# DenkyD4.net
KiCad netlist of a schematic drawn in EAGLE
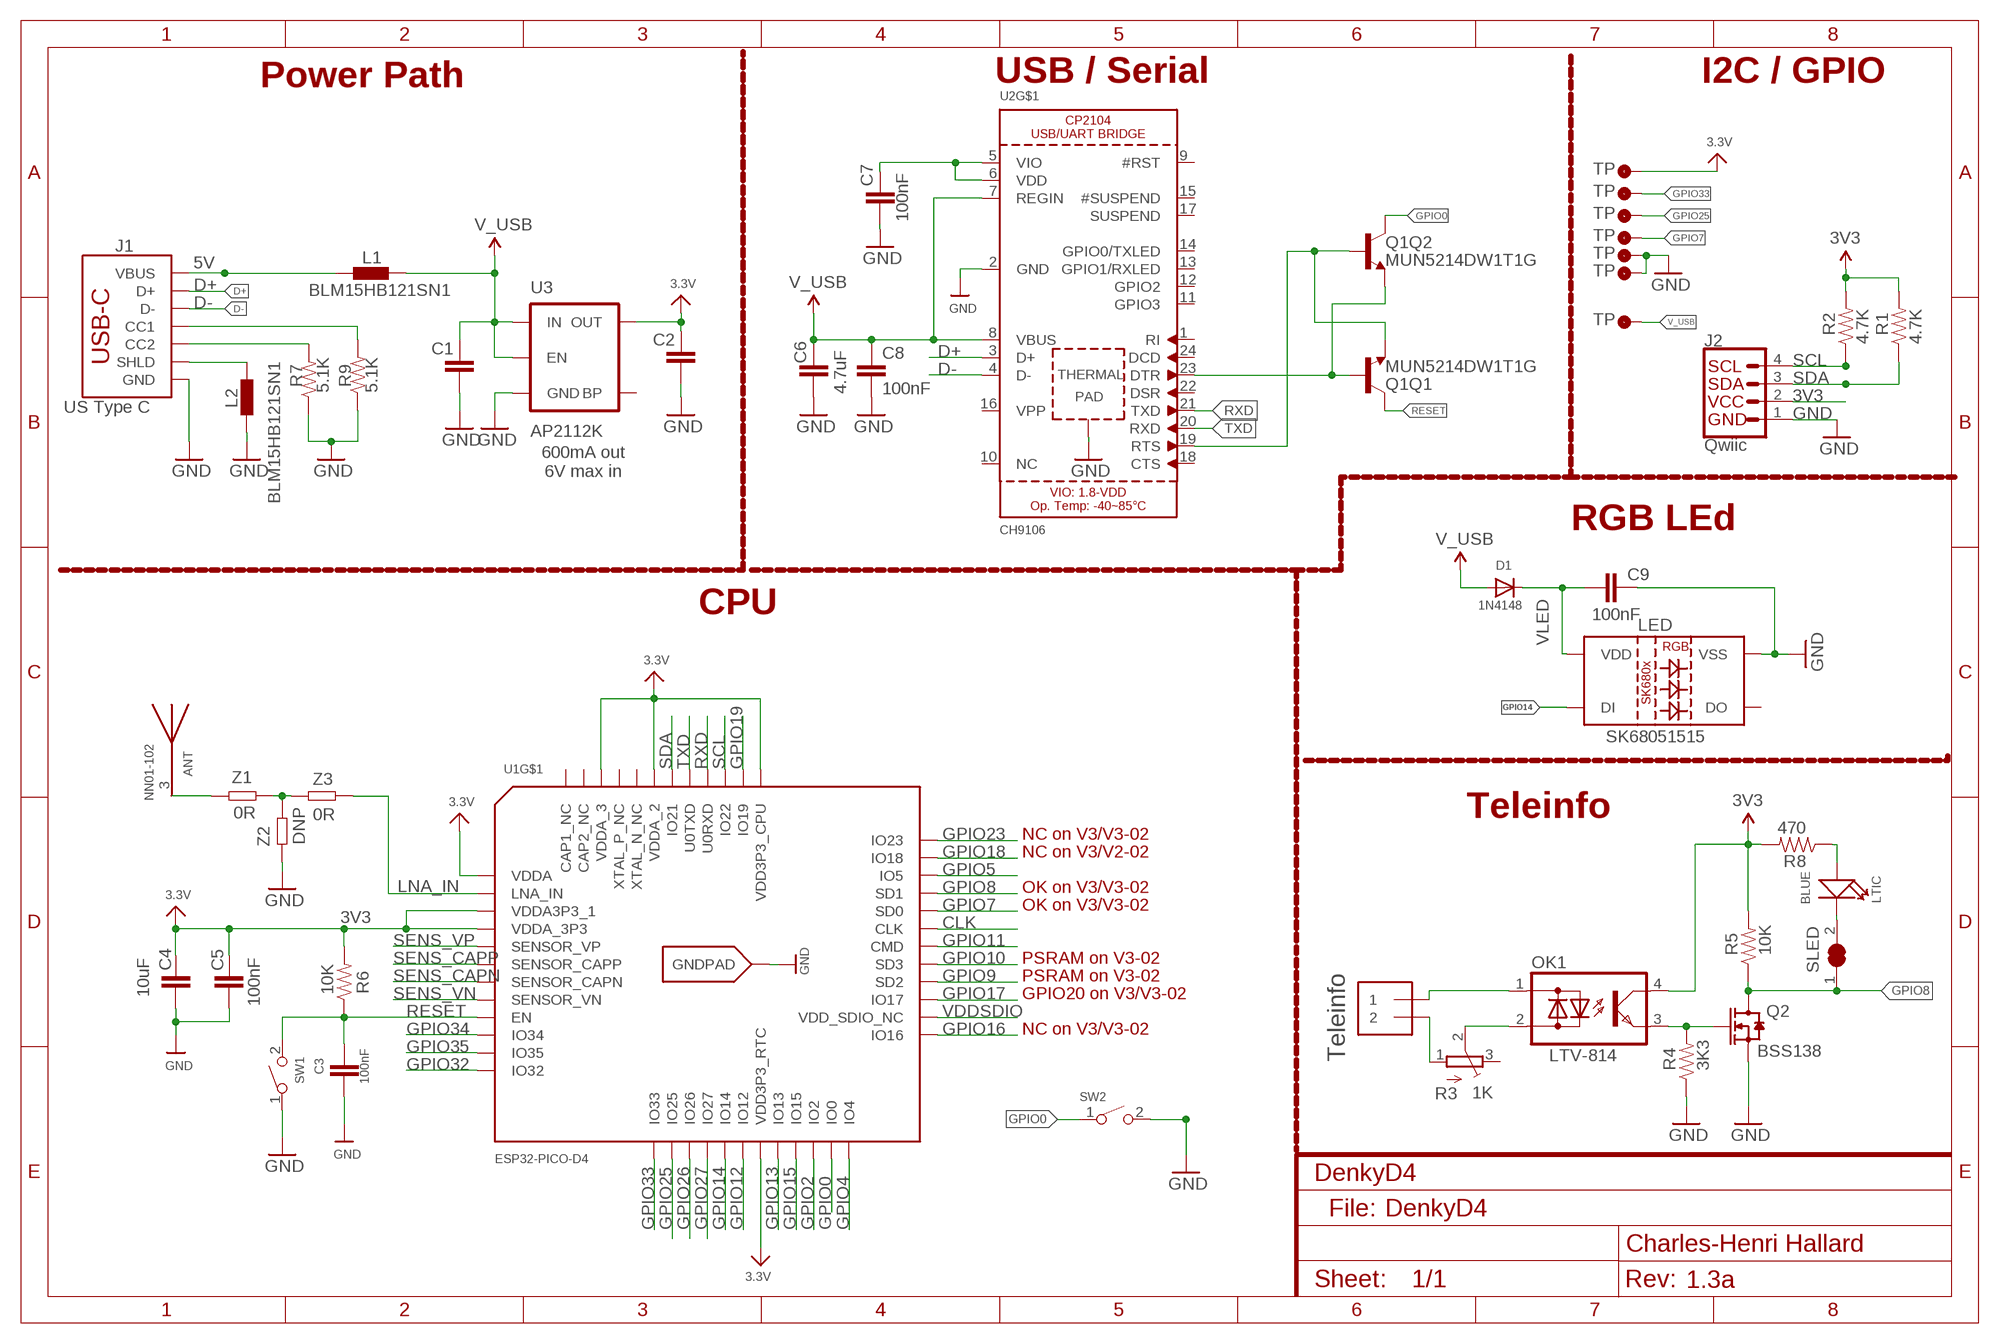
[diagram p0: schematic, sheet 1]

(export (version "E")
  (design (tool "Eeschema 10.0.6"))
  (components
    (comp (ref "ANT")
      (value "NN01-102")
      (footprint "eagle-import:XCVR_NN03-320")
      (libsource (lib "eagle-import") (part "NN01-102320"))
    )
    (comp (ref "C1")
      (value "1.0uF")
      (footprint "eagle-import:0402-CAP-OK")
      (libsource (lib "eagle-import") (part "CAP0402-CAP-OK"))
    )
    (comp (ref "C2")
      (value "1.0uF")
      (footprint "eagle-import:0402-CAP-OK")
      (libsource (lib "eagle-import") (part "CAP0402-CAP-OK"))
    )
    (comp (ref "C3")
      (value "100nF")
      (footprint "eagle-import:0402-CAP-OK")
      (libsource (lib "eagle-import") (part "CAP0402-CAP-OK"))
    )
    (comp (ref "C4")
      (value "10uF")
      (footprint "eagle-import:0402-CAP-OK")
      (libsource (lib "eagle-import") (part "CAP0402-CAP-OK"))
    )
    (comp (ref "C5")
      (value "100nF")
      (footprint "eagle-import:0402-CAP-OK")
      (libsource (lib "eagle-import") (part "CAP0402-CAP-OK"))
    )
    (comp (ref "C6")
      (value "4.7uF")
      (footprint "eagle-import:0402-CAP-OK")
      (libsource (lib "eagle-import") (part "CAP0402-CAP-OK"))
    )
    (comp (ref "C7")
      (value "100nF")
      (footprint "eagle-import:0402-CAP-OK")
      (libsource (lib "eagle-import") (part "CAP0402-CAP-OK"))
    )
    (comp (ref "C8")
      (value "100nF")
      (footprint "eagle-import:0402-CAP-OK")
      (libsource (lib "eagle-import") (part "CAP0402-CAP-OK"))
    )
    (comp (ref "C9")
      (value "100nF")
      (footprint "eagle-import:0402-CAP-OK")
      (libsource (lib "eagle-import") (part "CAP0402-CAP-OK"))
    )
    (comp (ref "D1")
      (value "1N4148")
      (footprint "eagle-import:SOD-523")
      (libsource (lib "eagle-import") (part "DIODESOD-523"))
    )
    (comp (ref "J1")
      (value "US Type C")
      (footprint "eagle-import:USB-C-16P-4LAYER-ISOLATED")
      (libsource (lib "eagle-import") (part "USB_C_4-LAYER-ISOLATED"))
    )
    (comp (ref "J2")
      (value "Qwiic")
      (footprint "eagle-import:JST04_1MM_VERT")
      (libsource (lib "eagle-import") (part "QWIIC_CONNECTOR"))
    )
    (comp (ref "J3")
      (value "KF2EDGR-3.81-2P")
      (footprint "eagle-import:1X2-3.5MM")
      (libsource (lib "eagle-import") (part "1X2-3.5MM-3.5MM"))
    )
    (comp (ref "L1")
      (value "BLM15HB121SN1")
      (footprint "eagle-import:0402")
      (libsource (lib "eagle-import") (part "BLM15HB121SN1"))
    )
    (comp (ref "L2")
      (value "BLM15HB121SN1")
      (footprint "eagle-import:0402")
      (libsource (lib "eagle-import") (part "BLM15HB121SN1"))
    )
    (comp (ref "LED")
      (value "SK68051515")
      (footprint "eagle-import:SK6805-1515")
      (libsource (lib "eagle-import") (part "SK68051515"))
    )
    (comp (ref "LTIC")
      (value "BLUE")
      (footprint "eagle-import:LED-0402")
      (fields (field (name "MPN") "BL-HB337A-AV-TRB"))
      (libsource (lib "eagle-import") (part "SMD-LED-CLEAR-BLUE(0402)"))
    )
    (comp (ref "OK1")
      (value "LTV-814")
      (footprint "eagle-import:DIL4-SMD")
      (fields (field (name "MF") "VISHAY/TELEFUNKEN") (field (name "MPN") "SFH6206-3"))
      (libsource (lib "eagle-import") (part "SFH6206"))
    )
    (comp (ref "Q1")
      (value "MUN5214DW1T1G")
      (footprint "eagle-import:DUAL_NPN_SC70-6")
      (libsource (lib "eagle-import") (part "MBT3904DW1T1"))
    )
    (comp (ref "Q2")
      (value "BSS138")
      (footprint "eagle-import:SOT-323-3")
      (libsource (lib "eagle-import") (part "SMD-MOSFET-N-CH-20V-2.1A-CJ2302(SOT-23)"))
    )
    (comp (ref "R1")
      (value "4.7K")
      (footprint "eagle-import:0402-RES")
      (libsource (lib "eagle-import") (part "_c2h_RESISTOR0402-RES"))
    )
    (comp (ref "R2")
      (value "4.7K")
      (footprint "eagle-import:0402-RES")
      (libsource (lib "eagle-import") (part "_c2h_RESISTOR0402-RES"))
    )
    (comp (ref "R3")
      (value "1K")
      (footprint "eagle-import:TC33X")
      (libsource (lib "eagle-import") (part "TRIMPOTTC33X"))
    )
    (comp (ref "R4")
      (value "3K3")
      (footprint "eagle-import:0402-RES")
      (libsource (lib "eagle-import") (part "_c2h_RESISTOR0402-RES"))
    )
    (comp (ref "R5")
      (value "10K")
      (footprint "eagle-import:0402-RES")
      (libsource (lib "eagle-import") (part "_c2h_RESISTOR0402-RES"))
    )
    (comp (ref "R6")
      (value "10K")
      (footprint "eagle-import:0402-RES")
      (libsource (lib "eagle-import") (part "_c2h_RESISTOR0402-RES"))
    )
    (comp (ref "R7")
      (value "5.1K")
      (footprint "eagle-import:0402-RES")
      (libsource (lib "eagle-import") (part "_c2h_RESISTOR0402-RES"))
    )
    (comp (ref "R8")
      (value "470")
      (footprint "eagle-import:0402-RES")
      (libsource (lib "eagle-import") (part "RESISTOR0402-RES"))
    )
    (comp (ref "R9")
      (value "5.1K")
      (footprint "eagle-import:0402-RES")
      (libsource (lib "eagle-import") (part "_c2h_RESISTOR0402-RES"))
    )
    (comp (ref "SLED")
      (value "SOLDERJUMPER_CLOSED")
      (footprint "eagle-import:SOLDERJUMPER_CLOSEDWIRE")
      (libsource (lib "eagle-import") (part "SOLDERJUMPER_CLOSED"))
    )
    (comp (ref "SW1")
      (value "RESET")
      (footprint "eagle-import:C498294")
      (libsource (lib "eagle-import") (part "SMD-BUTTON(2P-3.0X2.5X1.2+0.4MM)"))
    )
    (comp (ref "SW2")
      (value "SMD-BUTTON(2P-3.0X2.5X1.2+0.4MM)")
      (footprint "eagle-import:C498294")
      (libsource (lib "eagle-import") (part "SMD-BUTTON(2P-3.0X2.5X1.2+0.4MM)"))
    )
    (comp (ref "TGG")
      (value "TP3")
      (footprint "eagle-import:TP60_BOT")
      (libsource (lib "eagle-import") (part "TP3"))
    )
    (comp (ref "TGG1")
      (value "TP3")
      (footprint "eagle-import:TP60_BOT")
      (libsource (lib "eagle-import") (part "TP3"))
    )
    (comp (ref "TGG2")
      (value "TP3")
      (footprint "eagle-import:TP60_BOT")
      (libsource (lib "eagle-import") (part "TP3"))
    )
    (comp (ref "TP3")
      (value "TP3")
      (footprint "eagle-import:TP60_BOT")
      (libsource (lib "eagle-import") (part "TP3"))
    )
    (comp (ref "U$3")
      (value "TP3")
      (footprint "eagle-import:TP60_BOT")
      (libsource (lib "eagle-import") (part "TP3"))
    )
    (comp (ref "U$6")
      (value "TP3")
      (footprint "eagle-import:TP60_BOT")
      (libsource (lib "eagle-import") (part "TP3"))
    )
    (comp (ref "U$11")
      (value "TP3")
      (footprint "eagle-import:TP60_BOT")
      (libsource (lib "eagle-import") (part "TP3"))
    )
    (comp (ref "U1")
      (value "ESP32-PICO-D4")
      (footprint "eagle-import:PICO-D4-QFN48")
      (libsource (lib "eagle-import") (part "ESP32-PICO-D4"))
    )
    (comp (ref "U2")
      (value "CH9106")
      (footprint "eagle-import:QFN24_4MM_SMSC")
      (libsource (lib "eagle-import") (part "CP2104"))
    )
    (comp (ref "U3")
      (value "AP2112K")
      (footprint "eagle-import:SOT23-5")
      (libsource (lib "eagle-import") (part "V_REG_LDOSMD"))
    )
    (comp (ref "Z1")
      (value "0R")
      (footprint "eagle-import:0603-MATCHNET")
      (libsource (lib "eagle-import") (part "MATCHNET"))
    )
    (comp (ref "Z2")
      (value "DNP")
      (footprint "eagle-import:0603-MATCHNET")
      (libsource (lib "eagle-import") (part "MATCHNET"))
    )
    (comp (ref "Z3")
      (value "0R")
      (footprint "eagle-import:0603-MATCHNET")
      (libsource (lib "eagle-import") (part "MATCHNET"))
    )
  )
  (nets
    (net (code "1") (name "/5V") (class "Default")
      (node (ref "J1") (pin "VBUS1") (pinfunction "VBUS_VBUS1") (pintype "bidirectional"))
      (node (ref "J1") (pin "VBUS2") (pinfunction "VBUS_VBUS2") (pintype "bidirectional"))
      (node (ref "L1") (pin "1") (pinfunction "1_1") (pintype "passive"))
    )
    (net (code "2") (name "/CLK") (class "Default")
      (node (ref "U1") (pin "31") (pinfunction "CLK_31") (pintype "bidirectional"))
    )
    (net (code "3") (name "/GPIO2") (class "Default")
      (node (ref "U1") (pin "22") (pinfunction "IO2_22") (pintype "bidirectional"))
    )
    (net (code "4") (name "/GPIO4") (class "Default")
      (node (ref "U1") (pin "24") (pinfunction "IO4_24") (pintype "bidirectional"))
    )
    (net (code "5") (name "/GPIO5") (class "Default")
      (node (ref "U1") (pin "34") (pinfunction "IO5_34") (pintype "bidirectional"))
    )
    (net (code "6") (name "/GPIO9") (class "Default")
      (node (ref "U1") (pin "28") (pinfunction "SD2_28") (pintype "bidirectional"))
    )
    (net (code "7") (name "/GPIO10") (class "Default")
      (node (ref "U1") (pin "29") (pinfunction "SD3_29") (pintype "bidirectional"))
    )
    (net (code "8") (name "/GPIO11") (class "Default")
      (node (ref "U1") (pin "30") (pinfunction "CMD_30") (pintype "bidirectional"))
    )
    (net (code "9") (name "/GPIO12") (class "Default")
      (node (ref "U1") (pin "18") (pinfunction "IO12_18") (pintype "power_in"))
    )
    (net (code "10") (name "/GPIO13") (class "Default")
      (node (ref "U1") (pin "20") (pinfunction "IO13_20") (pintype "bidirectional"))
    )
    (net (code "11") (name "/GPIO15") (class "Default")
      (node (ref "U1") (pin "21") (pinfunction "IO15_21") (pintype "bidirectional"))
    )
    (net (code "12") (name "/GPIO16") (class "Default")
      (node (ref "U1") (pin "25") (pinfunction "IO16_25") (pintype "bidirectional"))
    )
    (net (code "13") (name "/GPIO17") (class "Default")
      (node (ref "U1") (pin "27") (pinfunction "IO17_27") (pintype "bidirectional"))
    )
    (net (code "14") (name "/GPIO18") (class "Default")
      (node (ref "U1") (pin "35") (pinfunction "IO18_35") (pintype "bidirectional"))
    )
    (net (code "15") (name "/GPIO19") (class "Default")
      (node (ref "U1") (pin "38") (pinfunction "IO19_38") (pintype "bidirectional"))
    )
    (net (code "16") (name "/GPIO23") (class "Default")
      (node (ref "U1") (pin "36") (pinfunction "IO23_36") (pintype "bidirectional"))
    )
    (net (code "17") (name "/GPIO26") (class "Default")
      (node (ref "U1") (pin "15") (pinfunction "IO26_15") (pintype "bidirectional"))
    )
    (net (code "18") (name "/GPIO27") (class "Default")
      (node (ref "U1") (pin "16") (pinfunction "IO27_16") (pintype "bidirectional"))
    )
    (net (code "19") (name "/GPIO32") (class "Default")
      (node (ref "U1") (pin "12") (pinfunction "IO32_12") (pintype "bidirectional"))
    )
    (net (code "20") (name "/GPIO34") (class "Default")
      (node (ref "U1") (pin "10") (pinfunction "IO34_10") (pintype "bidirectional"))
    )
    (net (code "21") (name "/GPIO35") (class "Default")
      (node (ref "U1") (pin "11") (pinfunction "IO35_11") (pintype "bidirectional"))
    )
    (net (code "22") (name "/LNA_IN") (class "Default")
      (node (ref "U1") (pin "2") (pinfunction "LNA_IN_2") (pintype "bidirectional"))
      (node (ref "Z3") (pin "2") (pinfunction "2_2") (pintype "passive"))
    )
    (net (code "23") (name "/SCL") (class "Default")
      (node (ref "J2") (pin "4") (pinfunction "4_4") (pintype "passive"))
      (node (ref "R2") (pin "1") (pinfunction "1_1") (pintype "passive"))
      (node (ref "U1") (pin "39") (pinfunction "IO22_39") (pintype "bidirectional"))
    )
    (net (code "24") (name "/SDA") (class "Default")
      (node (ref "J2") (pin "3") (pinfunction "3_3") (pintype "passive"))
      (node (ref "R1") (pin "1") (pinfunction "1_1") (pintype "passive"))
      (node (ref "U1") (pin "42") (pinfunction "IO21_42") (pintype "power_in"))
    )
    (net (code "25") (name "/SENS_CAPN") (class "Default")
      (node (ref "U1") (pin "7") (pinfunction "SENSOR_CAPN_7") (pintype "power_in"))
    )
    (net (code "26") (name "/SENS_CAPP") (class "Default")
      (node (ref "U1") (pin "6") (pinfunction "SENSOR_CAPP_6") (pintype "bidirectional"))
    )
    (net (code "27") (name "/SENS_VN") (class "Default")
      (node (ref "U1") (pin "8") (pinfunction "SENSOR_VN_8") (pintype "bidirectional"))
    )
    (net (code "28") (name "/SENS_VP") (class "Default")
      (node (ref "U1") (pin "5") (pinfunction "SENSOR_VP_5") (pintype "bidirectional"))
    )
    (net (code "29") (name "/VDDSDIO") (class "Default")
      (node (ref "U1") (pin "26") (pinfunction "VDD_SDIO_NC_26") (pintype "bidirectional"))
    )
    (net (code "30") (name "/VLED") (class "Default")
      (node (ref "C9") (pin "1") (pinfunction "1_1") (pintype "passive"))
      (node (ref "D1") (pin "K") (pinfunction "C_K") (pintype "passive"))
      (node (ref "LED") (pin "2") (pinfunction "VDD_2") (pintype "bidirectional"))
    )
    (net (code "31") (name "3.3V") (class "Default")
      (node (ref "C2") (pin "1") (pinfunction "1_1") (pintype "passive"))
      (node (ref "C4") (pin "1") (pinfunction "1_1") (pintype "passive"))
      (node (ref "C5") (pin "1") (pinfunction "1_1") (pintype "passive"))
      (node (ref "J2") (pin "2") (pinfunction "2_2") (pintype "power_in"))
      (node (ref "OK1") (pin "4") (pinfunction "C_4") (pintype "passive"))
      (node (ref "R1") (pin "2") (pinfunction "2_2") (pintype "passive"))
      (node (ref "R2") (pin "2") (pinfunction "2_2") (pintype "passive"))
      (node (ref "R5") (pin "2") (pinfunction "2_2") (pintype "passive"))
      (node (ref "R6") (pin "2") (pinfunction "2_2") (pintype "passive"))
      (node (ref "R8") (pin "2") (pinfunction "2_2") (pintype "passive"))
      (node (ref "TP3") (pin "P$1") (pinfunction "TP_P$1") (pintype "bidirectional"))
      (node (ref "U1") (pin "1") (pinfunction "VDDA_1") (pintype "bidirectional"))
      (node (ref "U1") (pin "19") (pinfunction "VDD3P3_RTC_19") (pintype "bidirectional"))
      (node (ref "U1") (pin "3") (pinfunction "VDDA3P3_1_3") (pintype "bidirectional"))
      (node (ref "U1") (pin "37") (pinfunction "VDD3P3_CPU_37") (pintype "bidirectional"))
      (node (ref "U1") (pin "4") (pinfunction "VDDA_3P3_4") (pintype "bidirectional"))
      (node (ref "U1") (pin "43") (pinfunction "VDDA_2_43") (pintype "bidirectional"))
      (node (ref "U1") (pin "46") (pinfunction "VDDA_3_46") (pintype "bidirectional"))
      (node (ref "U3") (pin "5") (pinfunction "OUT_5") (pintype "passive"))
    )
    (net (code "32") (name "D+") (class "Default")
      (node (ref "J1") (pin "A6") (pinfunction "D+_A6") (pintype "bidirectional"))
      (node (ref "J1") (pin "B6") (pinfunction "D+_B6") (pintype "bidirectional"))
      (node (ref "U2") (pin "3") (pinfunction "D+_3") (pintype "bidirectional"))
    )
    (net (code "33") (name "D-") (class "Default")
      (node (ref "J1") (pin "A7") (pinfunction "D-_A7") (pintype "bidirectional"))
      (node (ref "J1") (pin "B7") (pinfunction "D-_B7") (pintype "bidirectional"))
      (node (ref "U2") (pin "4") (pinfunction "D-_4") (pintype "bidirectional"))
    )
    (net (code "34") (name "GND") (class "Default")
      (node (ref "C1") (pin "2") (pinfunction "2_2") (pintype "passive"))
      (node (ref "C2") (pin "2") (pinfunction "2_2") (pintype "passive"))
      (node (ref "C3") (pin "2") (pinfunction "2_2") (pintype "passive"))
      (node (ref "C4") (pin "2") (pinfunction "2_2") (pintype "passive"))
      (node (ref "C5") (pin "2") (pinfunction "2_2") (pintype "passive"))
      (node (ref "C6") (pin "1") (pinfunction "1_1") (pintype "passive"))
      (node (ref "C7") (pin "1") (pinfunction "1_1") (pintype "passive"))
      (node (ref "C8") (pin "2") (pinfunction "2_2") (pintype "passive"))
      (node (ref "C9") (pin "2") (pinfunction "2_2") (pintype "passive"))
      (node (ref "J1") (pin "GND") (pinfunction "GND_GND") (pintype "bidirectional"))
      (node (ref "J1") (pin "GND2") (pinfunction "GND_GND2") (pintype "bidirectional"))
      (node (ref "J2") (pin "1") (pinfunction "1_1") (pintype "power_in"))
      (node (ref "L2") (pin "2") (pinfunction "2_2") (pintype "passive"))
      (node (ref "LED") (pin "4") (pinfunction "VSS_4") (pintype "bidirectional"))
      (node (ref "Q2") (pin "2") (pinfunction "S_2") (pintype "passive"))
      (node (ref "R4") (pin "1") (pinfunction "1_1") (pintype "passive"))
      (node (ref "R7") (pin "1") (pinfunction "1_1") (pintype "passive"))
      (node (ref "R9") (pin "1") (pinfunction "1_1") (pintype "passive"))
      (node (ref "SW1") (pin "1") (pinfunction "1_1") (pintype "bidirectional"))
      (node (ref "SW2") (pin "2") (pinfunction "2_2") (pintype "bidirectional"))
      (node (ref "TGG") (pin "P$1") (pinfunction "TP_P$1") (pintype "bidirectional"))
      (node (ref "TGG1") (pin "P$1") (pinfunction "TP_P$1") (pintype "bidirectional"))
      (node (ref "U1") (pin "EXP") (pinfunction "GNDPAD_EXP") (pintype "power_in"))
      (node (ref "U2") (pin "2") (pinfunction "GND_2") (pintype "power_in"))
      (node (ref "U2") (pin "THERM") (pinfunction "TP_THERM") (pintype "power_in"))
      (node (ref "U3") (pin "2") (pinfunction "GND_2") (pintype "input"))
      (node (ref "Z2") (pin "2") (pinfunction "2_2") (pintype "passive"))
    )
    (net (code "35") (name "GPIO0") (class "Default")
      (node (ref "Q1") (pin "6") (pinfunction "C_6") (pintype "passive"))
      (node (ref "SW2") (pin "1") (pinfunction "1_1") (pintype "bidirectional"))
      (node (ref "U1") (pin "23") (pinfunction "IO0_23") (pintype "bidirectional"))
    )
    (net (code "36") (name "GPIO7") (class "Default")
      (node (ref "U$3") (pin "P$1") (pinfunction "TP_P$1") (pintype "bidirectional"))
      (node (ref "U1") (pin "32") (pinfunction "SD0_32") (pintype "bidirectional"))
    )
    (net (code "37") (name "GPIO8") (class "Default")
      (node (ref "Q2") (pin "3") (pinfunction "D_3") (pintype "passive"))
      (node (ref "R5") (pin "1") (pinfunction "1_1") (pintype "passive"))
      (node (ref "SLED") (pin "1") (pinfunction "1_1") (pintype "passive"))
      (node (ref "U1") (pin "33") (pinfunction "SD1_33") (pintype "bidirectional"))
    )
    (net (code "38") (name "GPIO14") (class "Default")
      (node (ref "LED") (pin "1") (pinfunction "DI_1") (pintype "bidirectional"))
      (node (ref "U1") (pin "17") (pinfunction "IO14_17") (pintype "bidirectional"))
    )
    (net (code "39") (name "GPIO25") (class "Default")
      (node (ref "U$11") (pin "P$1") (pinfunction "TP_P$1") (pintype "bidirectional"))
      (node (ref "U1") (pin "14") (pinfunction "IO25_14") (pintype "bidirectional"))
    )
    (net (code "40") (name "GPIO33") (class "Default")
      (node (ref "U$6") (pin "P$1") (pinfunction "TP_P$1") (pintype "bidirectional"))
      (node (ref "U1") (pin "13") (pinfunction "IO33_13") (pintype "bidirectional"))
    )
    (net (code "41") (name "Net-(ANT-1)") (class "Default")
      (node (ref "ANT") (pin "3") (pinfunction "1_3") (pintype "input"))
      (node (ref "Z1") (pin "2") (pinfunction "2_2") (pintype "passive"))
    )
    (net (code "42") (name "Net-(J1-CC1)") (class "Default")
      (node (ref "J1") (pin "A5") (pinfunction "CC1_A5") (pintype "bidirectional"))
      (node (ref "R9") (pin "2") (pinfunction "2_2") (pintype "passive"))
    )
    (net (code "43") (name "Net-(J1-CC2)") (class "Default")
      (node (ref "J1") (pin "B5") (pinfunction "CC2_B5") (pintype "bidirectional"))
      (node (ref "R7") (pin "2") (pinfunction "2_2") (pintype "passive"))
    )
    (net (code "44") (name "Net-(J1-SHLD-PadSHLD1)") (class "Default")
      (node (ref "J1") (pin "SHLD1") (pinfunction "SHLD_SHLD1") (pintype "bidirectional"))
      (node (ref "J1") (pin "SHLD2") (pinfunction "SHLD_SHLD2") (pintype "bidirectional"))
      (node (ref "J1") (pin "SHLD3") (pinfunction "SHLD_SHLD3") (pintype "bidirectional"))
      (node (ref "J1") (pin "SHLD4") (pinfunction "SHLD_SHLD4") (pintype "bidirectional"))
      (node (ref "J1") (pin "SHLD5") (pinfunction "SHLD_SHLD5") (pintype "bidirectional"))
      (node (ref "J1") (pin "SHLD6") (pinfunction "SHLD_SHLD6") (pintype "bidirectional"))
      (node (ref "J1") (pin "SHLD7") (pinfunction "SHLD_SHLD7") (pintype "bidirectional"))
      (node (ref "J1") (pin "SHLD8") (pinfunction "SHLD_SHLD8") (pintype "bidirectional"))
      (node (ref "L2") (pin "1") (pinfunction "1_1") (pintype "passive"))
    )
    (net (code "45") (name "Net-(LTIC-Pad+)") (class "Default")
      (node (ref "LTIC") (pin "+") (pinfunction "+_+") (pintype "passive"))
      (node (ref "R8") (pin "1") (pinfunction "1_1") (pintype "passive"))
    )
    (net (code "46") (name "Net-(LTIC-Pad-)") (class "Default")
      (node (ref "LTIC") (pin "-") (pinfunction "-_-") (pintype "passive"))
      (node (ref "SLED") (pin "2") (pinfunction "2_2") (pintype "passive"))
    )
    (net (code "47") (name "Net-(OK1-AC1)") (class "Default")
      (node (ref "J3") (pin "1") (pinfunction "1_1") (pintype "passive"))
      (node (ref "OK1") (pin "1") (pinfunction "AC1_1") (pintype "passive"))
    )
    (net (code "48") (name "Net-(OK1-AC2)") (class "Default")
      (node (ref "OK1") (pin "2") (pinfunction "AC2_2") (pintype "passive"))
      (node (ref "R3") (pin "2") (pinfunction "S_2") (pintype "passive"))
    )
    (net (code "49") (name "Net-(OK1-E)") (class "Default")
      (node (ref "OK1") (pin "3") (pinfunction "E_3") (pintype "passive"))
      (node (ref "Q2") (pin "1") (pinfunction "G_1") (pintype "passive"))
      (node (ref "R4") (pin "2") (pinfunction "2_2") (pintype "passive"))
    )
    (net (code "50") (name "Net-(Q1A-B)") (class "Default")
      (node (ref "Q1") (pin "1") (pinfunction "E_1") (pintype "passive"))
      (node (ref "Q1") (pin "5") (pinfunction "B_5") (pintype "passive"))
      (node (ref "U2") (pin "23") (pinfunction "DTR_23") (pintype "output"))
    )
    (net (code "51") (name "Net-(Q1A-E)") (class "Default")
      (node (ref "Q1") (pin "2") (pinfunction "B_2") (pintype "passive"))
      (node (ref "Q1") (pin "4") (pinfunction "E_4") (pintype "passive"))
      (node (ref "U2") (pin "19") (pinfunction "RTS_19") (pintype "output"))
    )
    (net (code "52") (name "Net-(R3-A)") (class "Default")
      (node (ref "J3") (pin "2") (pinfunction "2_2") (pintype "passive"))
      (node (ref "R3") (pin "1") (pinfunction "A_1") (pintype "passive"))
    )
    (net (code "53") (name "Net-(U2A-VDD)") (class "Default")
      (node (ref "C7") (pin "2") (pinfunction "2_2") (pintype "passive"))
      (node (ref "U2") (pin "5") (pinfunction "VIO_5") (pintype "power_in"))
      (node (ref "U2") (pin "6") (pinfunction "VDD_6") (pintype "power_in"))
    )
    (net (code "54") (name "Net-(Z1-Pad1)") (class "Default")
      (node (ref "Z1") (pin "1") (pinfunction "1_1") (pintype "passive"))
      (node (ref "Z2") (pin "1") (pinfunction "1_1") (pintype "passive"))
      (node (ref "Z3") (pin "1") (pinfunction "1_1") (pintype "passive"))
    )
    (net (code "55") (name "RESET") (class "Default")
      (node (ref "C3") (pin "1") (pinfunction "1_1") (pintype "passive"))
      (node (ref "Q1") (pin "3") (pinfunction "C_3") (pintype "passive"))
      (node (ref "R6") (pin "1") (pinfunction "1_1") (pintype "passive"))
      (node (ref "SW1") (pin "2") (pinfunction "2_2") (pintype "bidirectional"))
      (node (ref "U1") (pin "9") (pinfunction "EN_9") (pintype "bidirectional"))
    )
    (net (code "56") (name "RXD") (class "Default")
      (node (ref "U1") (pin "40") (pinfunction "U0RXD_40") (pintype "bidirectional"))
      (node (ref "U2") (pin "21") (pinfunction "TXD_21") (pintype "output"))
    )
    (net (code "57") (name "TXD") (class "Default")
      (node (ref "U1") (pin "41") (pinfunction "U0TXD_41") (pintype "bidirectional"))
      (node (ref "U2") (pin "20") (pinfunction "RXD_20") (pintype "input"))
    )
    (net (code "58") (name "V_USB") (class "Default")
      (node (ref "C1") (pin "1") (pinfunction "1_1") (pintype "passive"))
      (node (ref "C6") (pin "2") (pinfunction "2_2") (pintype "passive"))
      (node (ref "C8") (pin "1") (pinfunction "1_1") (pintype "passive"))
      (node (ref "D1") (pin "A") (pinfunction "A_A") (pintype "passive"))
      (node (ref "L1") (pin "2") (pinfunction "2_2") (pintype "passive"))
      (node (ref "TGG2") (pin "P$1") (pinfunction "TP_P$1") (pintype "bidirectional"))
      (node (ref "U2") (pin "7") (pinfunction "REGIN_7") (pintype "power_in"))
      (node (ref "U2") (pin "8") (pinfunction "VBUS_8") (pintype "power_in"))
      (node (ref "U3") (pin "1") (pinfunction "IN_1") (pintype "input"))
      (node (ref "U3") (pin "3") (pinfunction "EN_3") (pintype "input"))
    )
    (net (code "59") (name "unconnected-(LED-DO-Pad3)") (class "Default")
      (node (ref "LED") (pin "3") (pinfunction "DO_3") (pintype "bidirectional"))
    )
    (net (code "60") (name "unconnected-(R3-E-Pad3)") (class "Default")
      (node (ref "R3") (pin "3") (pinfunction "E_3") (pintype "passive"))
    )
    (net (code "61") (name "unconnected-(U1A-CAP1_NC-Pad48)") (class "Default")
      (node (ref "U1") (pin "48") (pinfunction "CAP1_NC_48") (pintype "bidirectional"))
    )
    (net (code "62") (name "unconnected-(U1A-CAP2_NC-Pad47)") (class "Default")
      (node (ref "U1") (pin "47") (pinfunction "CAP2_NC_47") (pintype "bidirectional"))
    )
    (net (code "63") (name "unconnected-(U1A-XTAL_N_NC-Pad44)") (class "Default")
      (node (ref "U1") (pin "44") (pinfunction "XTAL_N_NC_44") (pintype "bidirectional"))
    )
    (net (code "64") (name "unconnected-(U1A-XTAL_P_NC-Pad45)") (class "Default")
      (node (ref "U1") (pin "45") (pinfunction "XTAL_P_NC_45") (pintype "bidirectional"))
    )
    (net (code "65") (name "unconnected-(U2A-#RST-Pad9)") (class "Default")
      (node (ref "U2") (pin "9") (pinfunction "#RST_9") (pintype "bidirectional"))
    )
    (net (code "66") (name "unconnected-(U2A-#SUSPEND-Pad15)") (class "Default")
      (node (ref "U2") (pin "15") (pinfunction "#SUSPEND_15") (pintype "output"))
    )
    (net (code "67") (name "unconnected-(U2A-CTS-Pad18)") (class "Default")
      (node (ref "U2") (pin "18") (pinfunction "CTS_18") (pintype "input"))
    )
    (net (code "68") (name "unconnected-(U2A-DCD-Pad24)") (class "Default")
      (node (ref "U2") (pin "24") (pinfunction "DCD_24") (pintype "input"))
    )
    (net (code "69") (name "unconnected-(U2A-DSR-Pad22)") (class "Default")
      (node (ref "U2") (pin "22") (pinfunction "DSR_22") (pintype "input"))
    )
    (net (code "70") (name "unconnected-(U2A-GPIO0{slash}TXLED-Pad14)") (class "Default")
      (node (ref "U2") (pin "14") (pinfunction "GPIO0/TXLED_14") (pintype "bidirectional"))
    )
    (net (code "71") (name "unconnected-(U2A-GPIO1{slash}RXLED-Pad13)") (class "Default")
      (node (ref "U2") (pin "13") (pinfunction "GPIO1/RXLED_13") (pintype "bidirectional"))
    )
    (net (code "72") (name "unconnected-(U2A-GPIO2-Pad12)") (class "Default")
      (node (ref "U2") (pin "12") (pinfunction "GPIO2_12") (pintype "bidirectional"))
    )
    (net (code "73") (name "unconnected-(U2A-GPIO3-Pad11)") (class "Default")
      (node (ref "U2") (pin "11") (pinfunction "GPIO3_11") (pintype "bidirectional"))
    )
    (net (code "74") (name "unconnected-(U2A-NC-Pad10)") (class "Default")
      (node (ref "U2") (pin "10") (pinfunction "NC_10") (pintype "no_connect"))
    )
    (net (code "75") (name "unconnected-(U2A-RI-Pad1)") (class "Default")
      (node (ref "U2") (pin "1") (pinfunction "RI_1") (pintype "input"))
    )
    (net (code "76") (name "unconnected-(U2A-SUSPEND-Pad17)") (class "Default")
      (node (ref "U2") (pin "17") (pinfunction "SUSPEND_17") (pintype "output"))
    )
    (net (code "77") (name "unconnected-(U2A-VPP-Pad16)") (class "Default")
      (node (ref "U2") (pin "16") (pinfunction "VPP_16") (pintype "bidirectional"))
    )
    (net (code "78") (name "unconnected-(U3-BP-Pad4)") (class "Default")
      (node (ref "U3") (pin "4") (pinfunction "BP_4") (pintype "input"))
    )
  )
)
